# Sheet2.net
KiCad netlist of a schematic drawn in Altium Designer
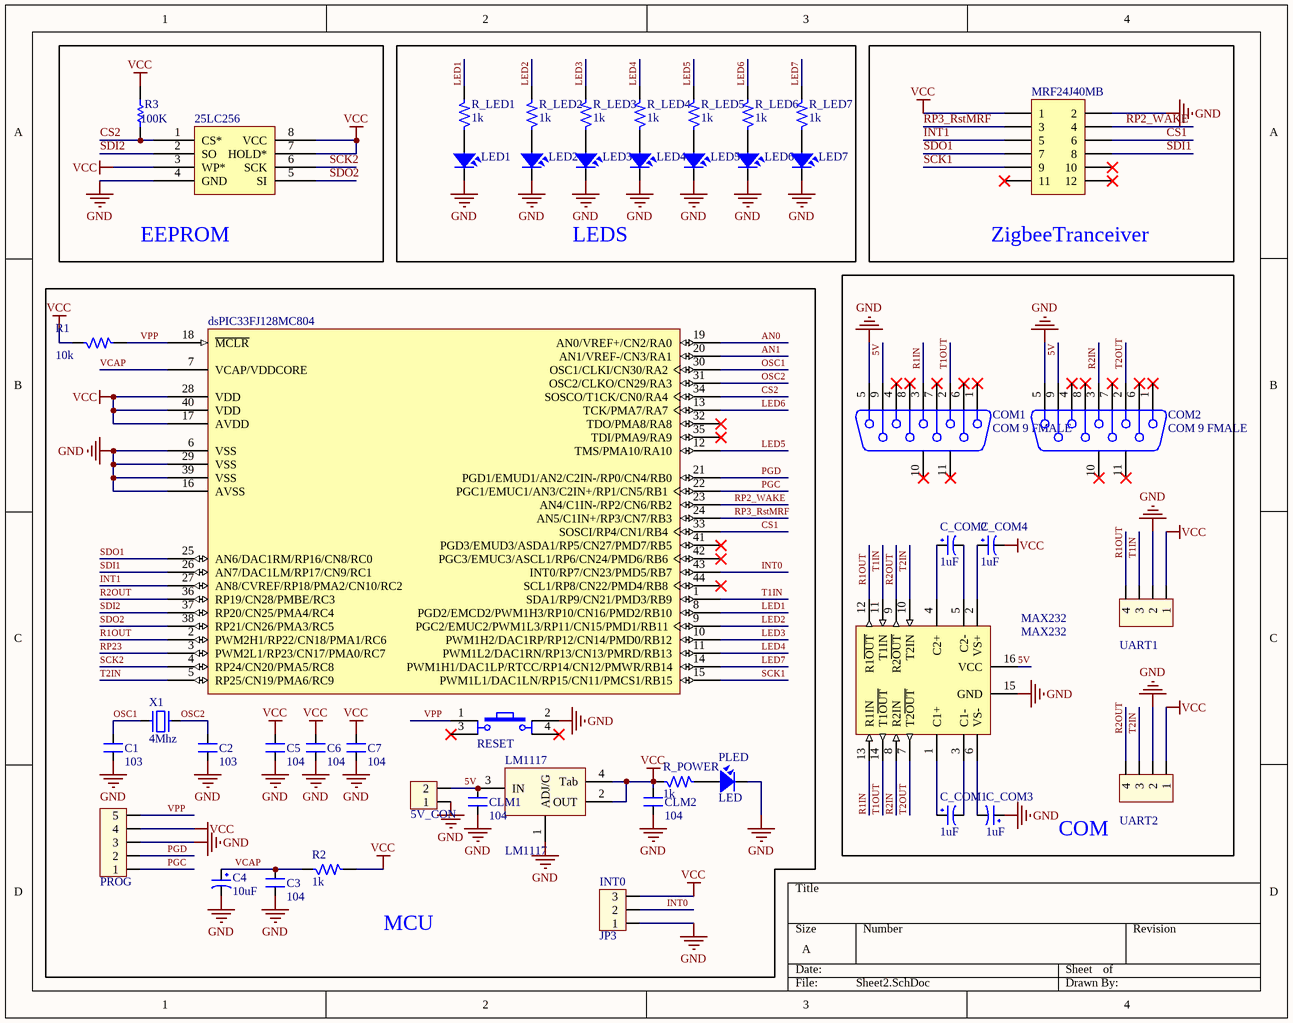
[diagram p0: Sheet2.SchDoc]

(export (version "E")
  (design (tool "Eeschema 10.0.6"))
  (components
    (comp (ref "5V_CON")
      (value "JP2")
      (footprint "CON2")
      (description "Connector 2")
      (libsource (lib "syhaunguyen") (part "Con2"))
    )
    (comp (ref "25LC256") (value "25LC256") (footprint "DIP-8") (libsource (lib "25LC256") (part "25LC256")))
    (comp (ref "C1")
      (value "103")
      (footprint "SM-0805")
      (description "Cap SMD")
      (libsource (lib "syhaunguyen") (part "CM"))
    )
    (comp (ref "C2")
      (value "103")
      (footprint "SM-0805")
      (description "Cap SMD")
      (libsource (lib "syhaunguyen") (part "CM"))
    )
    (comp (ref "C3")
      (value "104")
      (footprint "SM-0805")
      (description "Cap SMD")
      (libsource (lib "syhaunguyen") (part "CM"))
    )
    (comp (ref "C4")
      (value "10uF")
      (footprint "CP1/2")
      (description "Cap P  0,1uF < 22uF , 16 - 50V")
      (libsource (lib "") (part "CP1_1"))
    )
    (comp (ref "C5")
      (value "104")
      (footprint "SM-0805")
      (description "Cap SMD")
      (libsource (lib "syhaunguyen") (part "CM"))
    )
    (comp (ref "C6")
      (value "104")
      (footprint "SM-0805")
      (description "Cap SMD")
      (libsource (lib "syhaunguyen") (part "CM"))
    )
    (comp (ref "C7")
      (value "104")
      (footprint "SM-0805")
      (description "Cap SMD")
      (libsource (lib "syhaunguyen") (part "CM"))
    )
    (comp (ref "CLM1")
      (value "104")
      (footprint "SM-0805")
      (description "Cap np Cremic Value  104pF => 105pF")
      (libsource (lib "syhaunguyen") (part "CN2"))
    )
    (comp (ref "CLM2")
      (value "104")
      (footprint "SM-0805")
      (description "Cap np Cremic Value  104pF => 105pF")
      (libsource (lib "syhaunguyen") (part "CN2"))
    )
    (comp (ref "COM1")
      (value "COM 9 FMALE")
      (footprint "DSB 9-F")
      (description "COM 9")
      (fields (field (name "PUBLISHER") "Altium Limited"))
      (libsource (lib "syhaunguyen") (part "DSB9F"))
    )
    (comp (ref "COM2")
      (value "COM 9 FMALE")
      (footprint "DSB 9-F")
      (description "COM 9")
      (fields (field (name "PUBLISHER") "Altium Limited"))
      (libsource (lib "syhaunguyen") (part "DSB9F"))
    )
    (comp (ref "C_COM1")
      (value "1uF")
      (footprint "CP1/2")
      (description "Cap P  0,1uF < 22uF , 16 - 50V")
      (libsource (lib "syhaunguyen") (part "CP1"))
    )
    (comp (ref "C_COM2")
      (value "1uF")
      (footprint "CP1/2")
      (description "Cap P  0,1uF < 22uF , 16 - 50V")
      (libsource (lib "syhaunguyen") (part "CP1"))
    )
    (comp (ref "C_COM3")
      (value "1uF")
      (footprint "CP1/2")
      (description "Cap P  0,1uF < 22uF , 16 - 50V")
      (libsource (lib "syhaunguyen") (part "CP1"))
    )
    (comp (ref "C_COM4")
      (value "1uF")
      (footprint "CP1/2")
      (description "Cap P  0,1uF < 22uF , 16 - 50V")
      (libsource (lib "syhaunguyen") (part "CP1"))
    )
    (comp (ref "dsPIC33FJ128MC804")
      (value "DSPIC33FJ128MC804T-E/PT")
      (footprint "TQFP44-10x10-P0.8")
      (fields (field (name "PUBLISHER") "Altium Limited"))
      (libsource (lib "Microchip DSC 16-Bit dsPIC33F") (part "DSPIC33FJ128MC804T-E/PT"))
    )
    (comp (ref "INT0")
      (value "JP3")
      (footprint "CON3")
      (description "Connector 3")
      (libsource (lib "syhaunguyen") (part "Con3"))
    )
    (comp (ref "LED1")
      (value "LED")
      (footprint "SM-LED-Red")
      (description "Led  Vuong")
      (libsource (lib "syhaunguyen") (part "LED"))
    )
    (comp (ref "LED2")
      (value "LED")
      (footprint "SM-LED-Red")
      (description "Led  Vuong")
      (libsource (lib "syhaunguyen") (part "LED"))
    )
    (comp (ref "LED3")
      (value "LED")
      (footprint "SM-LED-Red")
      (description "Led  Vuong")
      (libsource (lib "syhaunguyen") (part "LED"))
    )
    (comp (ref "LED4")
      (value "LED")
      (footprint "SM-LED-Red")
      (description "Led  Vuong")
      (libsource (lib "syhaunguyen") (part "LED"))
    )
    (comp (ref "LED5")
      (value "LED")
      (footprint "SM-LED-Red")
      (description "Led  Vuong")
      (libsource (lib "syhaunguyen") (part "LED"))
    )
    (comp (ref "LED6")
      (value "LED")
      (footprint "SM-LED-Red")
      (description "Led  Vuong")
      (libsource (lib "syhaunguyen") (part "LED"))
    )
    (comp (ref "LED7")
      (value "LED")
      (footprint "SM-LED-Red")
      (description "Led  Vuong")
      (libsource (lib "syhaunguyen") (part "LED"))
    )
    (comp (ref "LM1117")
      (value "LM1117")
      (footprint "SOT223-4N")
      (description "3v3")
      (libsource (lib "syhaunguyen") (part "LM1117"))
    )
    (comp (ref "MAX232")
      (value "MAX232")
      (footprint "SOP16")
      (description "Dual EIA-232 Driver/Receiver")
      (libsource (lib "syhaunguyen") (part "MAX232"))
    )
    (comp (ref "MRF24J40MB")
      (value "Header 6X2")
      (footprint "HDR2X6")
      (description "Header, 6-Pin, Dual row")
      (fields (field (name "PUBLISHER") "Altium Limited"))
      (libsource (lib "Miscellaneous Connectors") (part "Header 6X2"))
    )
    (comp (ref "PLED")
      (value "LED")
      (footprint "LED-3")
      (description "Led  Vuong")
      (libsource (lib "syhaunguyen") (part "LED"))
    )
    (comp (ref "PROG")
      (value "JP5")
      (footprint "CON5")
      (description "Connector 5")
      (libsource (lib "syhaunguyen") (part "Con5"))
    )
    (comp (ref "R1")
      (value "10k")
      (footprint "C0805")
      (description "Resistor 1/4W")
      (libsource (lib "syhaunguyen") (part "R"))
    )
    (comp (ref "R2")
      (value "1k")
      (footprint "SM-0805")
      (description "Resistor 1/4W")
      (libsource (lib "syhaunguyen") (part "R"))
    )
    (comp (ref "R3")
      (value "100K")
      (footprint "C0805")
      (description "Semiconductor Resistor")
      (fields (field (name "Comment") "Res Semi") (field (name "PUBLISHER") "Altium Limited"))
      (libsource (lib "Miscellaneous Devices") (part "Res Semi"))
    )
    (comp (ref "RESET")
      (value "SW")
      (footprint "SW2")
      (description "Switch button 4 pin")
      (libsource (lib "syhaunguyen") (part "SW4"))
    )
    (comp (ref "R_LED1")
      (value "1k")
      (footprint "SM-0805")
      (description "Resistor 1/4W")
      (libsource (lib "syhaunguyen") (part "R"))
    )
    (comp (ref "R_LED2")
      (value "1k")
      (footprint "SM-0805")
      (description "Resistor 1/4W")
      (libsource (lib "syhaunguyen") (part "R"))
    )
    (comp (ref "R_LED3")
      (value "1k")
      (footprint "SM-0805")
      (description "Resistor 1/4W")
      (libsource (lib "syhaunguyen") (part "R"))
    )
    (comp (ref "R_LED4")
      (value "1k")
      (footprint "SM-0805")
      (description "Resistor 1/4W")
      (libsource (lib "syhaunguyen") (part "R"))
    )
    (comp (ref "R_LED5")
      (value "1k")
      (footprint "SM-0805")
      (description "Resistor 1/4W")
      (libsource (lib "syhaunguyen") (part "R"))
    )
    (comp (ref "R_LED6")
      (value "1k")
      (footprint "SM-0805")
      (description "Resistor 1/4W")
      (libsource (lib "syhaunguyen") (part "R"))
    )
    (comp (ref "R_LED7")
      (value "1k")
      (footprint "SM-0805")
      (description "Resistor 1/4W")
      (libsource (lib "syhaunguyen") (part "R"))
    )
    (comp (ref "R_POWER")
      (value "1k")
      (footprint "SM-0805")
      (description "Resistor 1/4W")
      (libsource (lib "syhaunguyen") (part "R"))
    )
    (comp (ref "UART1")
      (value "JP4")
      (footprint "CON4")
      (description "Connector 4")
      (libsource (lib "syhaunguyen") (part "Con4"))
    )
    (comp (ref "UART2")
      (value "JP4")
      (footprint "CON4")
      (description "Connector 4")
      (libsource (lib "syhaunguyen") (part "Con4"))
    )
    (comp (ref "X1")
      (value "4Mhz")
      (footprint "THACH ANH 12MHz")
      (description "Crystal For all Crystal 2pin.")
      (libsource (lib "syhaunguyen") (part "XT2"))
    )
  )
  (nets
    (net (code "1") (name "/5V") (class "Default")
      (node (ref "5V_CON") (pin "2") (pinfunction "2_2") (pintype "passive"))
      (node (ref "CLM1") (pin "2") (pinfunction "2_2") (pintype "passive"))
      (node (ref "COM1") (pin "9") (pinfunction "9_9") (pintype "passive"))
      (node (ref "COM2") (pin "9") (pinfunction "9_9") (pintype "passive"))
      (node (ref "LM1117") (pin "3") (pinfunction "IN_3") (pintype "passive"))
      (node (ref "MAX232") (pin "16") (pinfunction "VCC_16") (pintype "power_in"))
    )
    (net (code "2") (name "/AN0") (class "Default")
      (node (ref "dsPIC33FJ128MC804") (pin "19") (pinfunction "AN0/VREF+/CN2/RA0_19") (pintype "bidirectional"))
    )
    (net (code "3") (name "/AN1") (class "Default")
      (node (ref "dsPIC33FJ128MC804") (pin "20") (pinfunction "AN1/VREF-/CN3/RA1_20") (pintype "bidirectional"))
    )
    (net (code "4") (name "/CS1") (class "Default")
      (node (ref "MRF24J40MB") (pin "6") (pinfunction "6_6") (pintype "passive"))
      (node (ref "dsPIC33FJ128MC804") (pin "33") (pinfunction "SOSCI/RP4/CN1/RB4_33") (pintype "bidirectional"))
    )
    (net (code "5") (name "/CS2") (class "Default")
      (node (ref "25LC256") (pin "1") (pinfunction "CS*_1") (pintype "passive"))
      (node (ref "R3") (pin "1") (pinfunction "1_1") (pintype "passive"))
      (node (ref "dsPIC33FJ128MC804") (pin "34") (pinfunction "SOSCO/T1CK/CN0/RA4_34") (pintype "bidirectional"))
    )
    (net (code "6") (name "/INT0") (class "Default")
      (node (ref "INT0") (pin "2") (pinfunction "2_2") (pintype "passive"))
      (node (ref "dsPIC33FJ128MC804") (pin "43") (pinfunction "INT0/RP7/CN23/PMD5/RB7_43") (pintype "bidirectional"))
    )
    (net (code "7") (name "/INT1") (class "Default")
      (node (ref "MRF24J40MB") (pin "5") (pinfunction "5_5") (pintype "passive"))
      (node (ref "dsPIC33FJ128MC804") (pin "27") (pinfunction "AN8/CVREF/RP18/PMA2/CN10/RC2_27") (pintype "bidirectional"))
    )
    (net (code "8") (name "/LED1") (class "Default")
      (node (ref "R_LED1") (pin "2") (pinfunction "2_2") (pintype "passive"))
      (node (ref "dsPIC33FJ128MC804") (pin "8") (pinfunction "PGD2/EMCD2/PWM1H3/RP10/CN16/PMD2/RB10_8") (pintype "bidirectional"))
    )
    (net (code "9") (name "/LED2") (class "Default")
      (node (ref "R_LED2") (pin "2") (pinfunction "2_2") (pintype "passive"))
      (node (ref "dsPIC33FJ128MC804") (pin "9") (pinfunction "PGC2/EMUC2/PWM1L3/RP11/CN15/PMD1/RB11_9") (pintype "bidirectional"))
    )
    (net (code "10") (name "/LED3") (class "Default")
      (node (ref "R_LED3") (pin "2") (pinfunction "2_2") (pintype "passive"))
      (node (ref "dsPIC33FJ128MC804") (pin "10") (pinfunction "PWM1H2/DAC1RP/RP12/CN14/PMD0/RB12_10") (pintype "bidirectional"))
    )
    (net (code "11") (name "/LED4") (class "Default")
      (node (ref "R_LED4") (pin "2") (pinfunction "2_2") (pintype "passive"))
      (node (ref "dsPIC33FJ128MC804") (pin "11") (pinfunction "PWM1L2/DAC1RN/RP13/CN13/PMRD/RB13_11") (pintype "bidirectional"))
    )
    (net (code "12") (name "/LED5") (class "Default")
      (node (ref "R_LED5") (pin "2") (pinfunction "2_2") (pintype "passive"))
      (node (ref "dsPIC33FJ128MC804") (pin "12") (pinfunction "TMS/PMA10/RA10_12") (pintype "bidirectional"))
    )
    (net (code "13") (name "/LED6") (class "Default")
      (node (ref "R_LED6") (pin "2") (pinfunction "2_2") (pintype "passive"))
      (node (ref "dsPIC33FJ128MC804") (pin "13") (pinfunction "TCK/PMA7/RA7_13") (pintype "bidirectional"))
    )
    (net (code "14") (name "/LED7") (class "Default")
      (node (ref "R_LED7") (pin "2") (pinfunction "2_2") (pintype "passive"))
      (node (ref "dsPIC33FJ128MC804") (pin "14") (pinfunction "PWM1H1/DAC1LP/RTCC/RP14/CN12/PMWR/RB14_14") (pintype "bidirectional"))
    )
    (net (code "15") (name "/OSC1") (class "Default")
      (node (ref "C1") (pin "2") (pinfunction "2_2") (pintype "passive"))
      (node (ref "X1") (pin "1") (pinfunction "1_1") (pintype "passive"))
      (node (ref "dsPIC33FJ128MC804") (pin "30") (pinfunction "OSC1/CLKI/CN30/RA2_30") (pintype "bidirectional"))
    )
    (net (code "16") (name "/OSC2") (class "Default")
      (node (ref "C2") (pin "2") (pinfunction "2_2") (pintype "passive"))
      (node (ref "X1") (pin "2") (pinfunction "2_2") (pintype "passive"))
      (node (ref "dsPIC33FJ128MC804") (pin "31") (pinfunction "OSC2/CLKO/CN29/RA3_31") (pintype "bidirectional"))
    )
    (net (code "17") (name "/PGC") (class "Default")
      (node (ref "PROG") (pin "1") (pinfunction "1_1") (pintype "passive"))
      (node (ref "dsPIC33FJ128MC804") (pin "22") (pinfunction "PGC1/EMUC1/AN3/C2IN+/RP1/CN5/RB1_22") (pintype "bidirectional"))
    )
    (net (code "18") (name "/PGD") (class "Default")
      (node (ref "PROG") (pin "2") (pinfunction "2_2") (pintype "passive"))
      (node (ref "dsPIC33FJ128MC804") (pin "21") (pinfunction "PGD1/EMUD1/AN2/C2IN-/RP0/CN4/RB0_21") (pintype "bidirectional"))
    )
    (net (code "19") (name "/R1IN") (class "Default")
      (node (ref "COM1") (pin "3") (pinfunction "3_3") (pintype "passive"))
      (node (ref "MAX232") (pin "13") (pinfunction "R1IN_13") (pintype "input"))
    )
    (net (code "20") (name "/R1OUT") (class "Default")
      (node (ref "MAX232") (pin "12") (pinfunction "R1~{OUT}_12") (pintype "output"))
      (node (ref "UART1") (pin "4") (pinfunction "4_4") (pintype "passive"))
      (node (ref "dsPIC33FJ128MC804") (pin "2") (pinfunction "PWM2H1/RP22/CN18/PMA1/RC6_2") (pintype "bidirectional"))
    )
    (net (code "21") (name "/R2IN") (class "Default")
      (node (ref "COM2") (pin "3") (pinfunction "3_3") (pintype "passive"))
      (node (ref "MAX232") (pin "8") (pinfunction "R2IN_8") (pintype "input"))
    )
    (net (code "22") (name "/R2OUT") (class "Default")
      (node (ref "MAX232") (pin "9") (pinfunction "R2~{OUT}_9") (pintype "output"))
      (node (ref "UART2") (pin "4") (pinfunction "4_4") (pintype "passive"))
      (node (ref "dsPIC33FJ128MC804") (pin "36") (pinfunction "RP19/CN28/PMBE/RC3_36") (pintype "bidirectional"))
    )
    (net (code "23") (name "/RP2_WAKE") (class "Default")
      (node (ref "MRF24J40MB") (pin "4") (pinfunction "4_4") (pintype "passive"))
      (node (ref "dsPIC33FJ128MC804") (pin "23") (pinfunction "AN4/C1IN-/RP2/CN6/RB2_23") (pintype "bidirectional"))
    )
    (net (code "24") (name "/RP3_RstMRF") (class "Default")
      (node (ref "MRF24J40MB") (pin "3") (pinfunction "3_3") (pintype "passive"))
      (node (ref "dsPIC33FJ128MC804") (pin "24") (pinfunction "AN5/C1IN+/RP3/CN7/RB3_24") (pintype "bidirectional"))
    )
    (net (code "25") (name "/RP23") (class "Default")
      (node (ref "dsPIC33FJ128MC804") (pin "3") (pinfunction "PWM2L1/RP23/CN17/PMA0/RC7_3") (pintype "bidirectional"))
    )
    (net (code "26") (name "/SCK1") (class "Default")
      (node (ref "MRF24J40MB") (pin "9") (pinfunction "9_9") (pintype "passive"))
      (node (ref "dsPIC33FJ128MC804") (pin "15") (pinfunction "PWM1L1/DAC1LN/RP15/CN11/PMCS1/RB15_15") (pintype "bidirectional"))
    )
    (net (code "27") (name "/SCK2") (class "Default")
      (node (ref "25LC256") (pin "6") (pinfunction "SCK_6") (pintype "passive"))
      (node (ref "dsPIC33FJ128MC804") (pin "4") (pinfunction "RP24/CN20/PMA5/RC8_4") (pintype "bidirectional"))
    )
    (net (code "28") (name "/SDI1") (class "Default")
      (node (ref "MRF24J40MB") (pin "8") (pinfunction "8_8") (pintype "passive"))
      (node (ref "dsPIC33FJ128MC804") (pin "26") (pinfunction "AN7/DAC1LM/RP17/CN9/RC1_26") (pintype "bidirectional"))
    )
    (net (code "29") (name "/SDI2") (class "Default")
      (node (ref "25LC256") (pin "2") (pinfunction "SO_2") (pintype "passive"))
      (node (ref "dsPIC33FJ128MC804") (pin "37") (pinfunction "RP20/CN25/PMA4/RC4_37") (pintype "bidirectional"))
    )
    (net (code "30") (name "/SDO1") (class "Default")
      (node (ref "MRF24J40MB") (pin "7") (pinfunction "7_7") (pintype "passive"))
      (node (ref "dsPIC33FJ128MC804") (pin "25") (pinfunction "AN6/DAC1RM/RP16/CN8/RC0_25") (pintype "bidirectional"))
    )
    (net (code "31") (name "/SDO2") (class "Default")
      (node (ref "25LC256") (pin "5") (pinfunction "SI_5") (pintype "passive"))
      (node (ref "dsPIC33FJ128MC804") (pin "38") (pinfunction "RP21/CN26/PMA3/RC5_38") (pintype "bidirectional"))
    )
    (net (code "32") (name "/T1IN") (class "Default")
      (node (ref "MAX232") (pin "11") (pinfunction "T1IN_11") (pintype "input"))
      (node (ref "UART1") (pin "3") (pinfunction "3_3") (pintype "passive"))
      (node (ref "dsPIC33FJ128MC804") (pin "1") (pinfunction "SDA1/RP9/CN21/PMD3/RB9_1") (pintype "bidirectional"))
    )
    (net (code "33") (name "/T1OUT") (class "Default")
      (node (ref "COM1") (pin "2") (pinfunction "2_2") (pintype "passive"))
      (node (ref "MAX232") (pin "14") (pinfunction "T1~{OUT}_14") (pintype "output"))
    )
    (net (code "34") (name "/T2IN") (class "Default")
      (node (ref "MAX232") (pin "10") (pinfunction "T2IN_10") (pintype "input"))
      (node (ref "UART2") (pin "3") (pinfunction "3_3") (pintype "passive"))
      (node (ref "dsPIC33FJ128MC804") (pin "5") (pinfunction "RP25/CN19/PMA6/RC9_5") (pintype "bidirectional"))
    )
    (net (code "35") (name "/T2OUT") (class "Default")
      (node (ref "COM2") (pin "2") (pinfunction "2_2") (pintype "passive"))
      (node (ref "MAX232") (pin "7") (pinfunction "T2~{OUT}_7") (pintype "output"))
    )
    (net (code "36") (name "/VCAP") (class "Default")
      (node (ref "C3") (pin "2") (pinfunction "2_2") (pintype "passive"))
      (node (ref "C4") (pin "1") (pinfunction "1_1") (pintype "passive"))
      (node (ref "R2") (pin "1") (pinfunction "1_1") (pintype "passive"))
      (node (ref "dsPIC33FJ128MC804") (pin "7") (pinfunction "VCAP/VDDCORE_7") (pintype "power_in"))
    )
    (net (code "37") (name "/VPP") (class "Default")
      (node (ref "PROG") (pin "5") (pinfunction "5_5") (pintype "passive"))
      (node (ref "R1") (pin "2") (pinfunction "2_2") (pintype "passive"))
      (node (ref "RESET") (pin "1") (pintype "passive"))
      (node (ref "dsPIC33FJ128MC804") (pin "18") (pinfunction "~{MCLR}_18") (pintype "input"))
    )
    (net (code "38") (name "GND") (class "Default")
      (node (ref "25LC256") (pin "4") (pinfunction "GND_4") (pintype "power_in"))
      (node (ref "5V_CON") (pin "1") (pinfunction "1_1") (pintype "passive"))
      (node (ref "C1") (pin "1") (pinfunction "1_1") (pintype "passive"))
      (node (ref "C2") (pin "1") (pinfunction "1_1") (pintype "passive"))
      (node (ref "C3") (pin "1") (pinfunction "1_1") (pintype "passive"))
      (node (ref "C4") (pin "2") (pinfunction "2_2") (pintype "passive"))
      (node (ref "C5") (pin "1") (pinfunction "1_1") (pintype "passive"))
      (node (ref "C6") (pin "1") (pinfunction "1_1") (pintype "passive"))
      (node (ref "C7") (pin "1") (pinfunction "1_1") (pintype "passive"))
      (node (ref "CLM1") (pin "1") (pinfunction "1_1") (pintype "passive"))
      (node (ref "CLM2") (pin "1") (pinfunction "1_1") (pintype "passive"))
      (node (ref "COM1") (pin "5") (pinfunction "5_5") (pintype "passive"))
      (node (ref "COM2") (pin "5") (pinfunction "5_5") (pintype "passive"))
      (node (ref "C_COM3") (pin "1") (pinfunction "1_1") (pintype "passive"))
      (node (ref "INT0") (pin "1") (pinfunction "1_1") (pintype "passive"))
      (node (ref "LED1") (pin "2") (pinfunction "2_2") (pintype "passive"))
      (node (ref "LED2") (pin "2") (pinfunction "2_2") (pintype "passive"))
      (node (ref "LED3") (pin "2") (pinfunction "2_2") (pintype "passive"))
      (node (ref "LED4") (pin "2") (pinfunction "2_2") (pintype "passive"))
      (node (ref "LED5") (pin "2") (pinfunction "2_2") (pintype "passive"))
      (node (ref "LED6") (pin "2") (pinfunction "2_2") (pintype "passive"))
      (node (ref "LED7") (pin "2") (pinfunction "2_2") (pintype "passive"))
      (node (ref "LM1117") (pin "1") (pinfunction "ADJ/G_1") (pintype "passive"))
      (node (ref "MAX232") (pin "15") (pinfunction "GND_15") (pintype "power_in"))
      (node (ref "MRF24J40MB") (pin "2") (pinfunction "2_2") (pintype "passive"))
      (node (ref "PLED") (pin "2") (pinfunction "2_2") (pintype "passive"))
      (node (ref "PROG") (pin "3") (pinfunction "3_3") (pintype "passive"))
      (node (ref "RESET") (pin "2") (pintype "passive"))
      (node (ref "UART1") (pin "2") (pinfunction "2_2") (pintype "passive"))
      (node (ref "UART2") (pin "2") (pinfunction "2_2") (pintype "passive"))
      (node (ref "dsPIC33FJ128MC804") (pin "16") (pinfunction "AVSS_16") (pintype "power_in"))
      (node (ref "dsPIC33FJ128MC804") (pin "29") (pinfunction "VSS_29") (pintype "power_in"))
      (node (ref "dsPIC33FJ128MC804") (pin "39") (pinfunction "VSS_39") (pintype "power_in"))
      (node (ref "dsPIC33FJ128MC804") (pin "6") (pinfunction "VSS_6") (pintype "power_in"))
    )
    (net (code "39") (name "Net-(LED1-Pad1)") (class "Default")
      (node (ref "LED1") (pin "1") (pinfunction "1_1") (pintype "passive"))
      (node (ref "R_LED1") (pin "1") (pinfunction "1_1") (pintype "passive"))
    )
    (net (code "40") (name "Net-(LED2-Pad1)") (class "Default")
      (node (ref "LED2") (pin "1") (pinfunction "1_1") (pintype "passive"))
      (node (ref "R_LED2") (pin "1") (pinfunction "1_1") (pintype "passive"))
    )
    (net (code "41") (name "Net-(LED3-Pad1)") (class "Default")
      (node (ref "LED3") (pin "1") (pinfunction "1_1") (pintype "passive"))
      (node (ref "R_LED3") (pin "1") (pinfunction "1_1") (pintype "passive"))
    )
    (net (code "42") (name "Net-(LED4-Pad1)") (class "Default")
      (node (ref "LED4") (pin "1") (pinfunction "1_1") (pintype "passive"))
      (node (ref "R_LED4") (pin "1") (pinfunction "1_1") (pintype "passive"))
    )
    (net (code "43") (name "Net-(LED5-Pad1)") (class "Default")
      (node (ref "LED5") (pin "1") (pinfunction "1_1") (pintype "passive"))
      (node (ref "R_LED5") (pin "1") (pinfunction "1_1") (pintype "passive"))
    )
    (net (code "44") (name "Net-(LED6-Pad1)") (class "Default")
      (node (ref "LED6") (pin "1") (pinfunction "1_1") (pintype "passive"))
      (node (ref "R_LED6") (pin "1") (pinfunction "1_1") (pintype "passive"))
    )
    (net (code "45") (name "Net-(LED7-Pad1)") (class "Default")
      (node (ref "LED7") (pin "1") (pinfunction "1_1") (pintype "passive"))
      (node (ref "R_LED7") (pin "1") (pinfunction "1_1") (pintype "passive"))
    )
    (net (code "46") (name "Net-(MAX232-C1+)") (class "Default")
      (node (ref "C_COM1") (pin "1") (pinfunction "1_1") (pintype "passive"))
      (node (ref "MAX232") (pin "1") (pinfunction "C1+_1") (pintype "passive"))
    )
    (net (code "47") (name "Net-(MAX232-C1-)") (class "Default")
      (node (ref "C_COM1") (pin "2") (pinfunction "2_2") (pintype "passive"))
      (node (ref "MAX232") (pin "3") (pinfunction "C1-_3") (pintype "passive"))
    )
    (net (code "48") (name "Net-(MAX232-C2+)") (class "Default")
      (node (ref "C_COM2") (pin "1") (pinfunction "1_1") (pintype "passive"))
      (node (ref "MAX232") (pin "4") (pinfunction "C2+_4") (pintype "passive"))
    )
    (net (code "49") (name "Net-(MAX232-C2-)") (class "Default")
      (node (ref "C_COM2") (pin "2") (pinfunction "2_2") (pintype "passive"))
      (node (ref "MAX232") (pin "5") (pinfunction "C2-_5") (pintype "passive"))
    )
    (net (code "50") (name "Net-(MAX232-VS+)") (class "Default")
      (node (ref "C_COM4") (pin "1") (pinfunction "1_1") (pintype "passive"))
      (node (ref "MAX232") (pin "2") (pinfunction "VS+_2") (pintype "power_in"))
    )
    (net (code "51") (name "Net-(MAX232-VS-)") (class "Default")
      (node (ref "C_COM3") (pin "2") (pinfunction "2_2") (pintype "passive"))
      (node (ref "MAX232") (pin "6") (pinfunction "VS-_6") (pintype "power_in"))
    )
    (net (code "52") (name "Net-(PLED-Pad1)") (class "Default")
      (node (ref "PLED") (pin "1") (pinfunction "1_1") (pintype "passive"))
      (node (ref "R_POWER") (pin "2") (pinfunction "2_2") (pintype "passive"))
    )
    (net (code "53") (name "VCC") (class "Default")
      (node (ref "25LC256") (pin "3") (pinfunction "WP*_3") (pintype "passive"))
      (node (ref "25LC256") (pin "7") (pinfunction "HOLD*_7") (pintype "passive"))
      (node (ref "25LC256") (pin "8") (pinfunction "VCC_8") (pintype "power_in"))
      (node (ref "C5") (pin "2") (pinfunction "2_2") (pintype "passive"))
      (node (ref "C6") (pin "2") (pinfunction "2_2") (pintype "passive"))
      (node (ref "C7") (pin "2") (pinfunction "2_2") (pintype "passive"))
      (node (ref "CLM2") (pin "2") (pinfunction "2_2") (pintype "passive"))
      (node (ref "C_COM4") (pin "2") (pinfunction "2_2") (pintype "passive"))
      (node (ref "INT0") (pin "3") (pinfunction "3_3") (pintype "passive"))
      (node (ref "LM1117") (pin "2") (pinfunction "OUT_2") (pintype "passive"))
      (node (ref "LM1117") (pin "4") (pinfunction "Tab_4") (pintype "passive"))
      (node (ref "MRF24J40MB") (pin "1") (pinfunction "1_1") (pintype "passive"))
      (node (ref "PROG") (pin "4") (pinfunction "4_4") (pintype "passive"))
      (node (ref "R1") (pin "1") (pinfunction "1_1") (pintype "passive"))
      (node (ref "R2") (pin "2") (pinfunction "2_2") (pintype "passive"))
      (node (ref "R3") (pin "2") (pinfunction "2_2") (pintype "passive"))
      (node (ref "R_POWER") (pin "1") (pinfunction "1_1") (pintype "passive"))
      (node (ref "UART1") (pin "1") (pinfunction "1_1") (pintype "passive"))
      (node (ref "UART2") (pin "1") (pinfunction "1_1") (pintype "passive"))
      (node (ref "dsPIC33FJ128MC804") (pin "17") (pinfunction "AVDD_17") (pintype "power_in"))
      (node (ref "dsPIC33FJ128MC804") (pin "28") (pinfunction "VDD_28") (pintype "power_in"))
      (node (ref "dsPIC33FJ128MC804") (pin "40") (pinfunction "VDD_40") (pintype "power_in"))
    )
    (net (code "54") (name "unconnected-(COM1-MH1-Pad10)") (class "Default")
      (node (ref "COM1") (pin "10") (pinfunction "MH1_10") (pintype "passive+no_connect"))
    )
    (net (code "55") (name "unconnected-(COM1-MH2-Pad11)") (class "Default")
      (node (ref "COM1") (pin "11") (pinfunction "MH2_11") (pintype "passive+no_connect"))
    )
    (net (code "56") (name "unconnected-(COM1-Pad1)") (class "Default")
      (node (ref "COM1") (pin "1") (pinfunction "1_1") (pintype "passive+no_connect"))
    )
    (net (code "57") (name "unconnected-(COM1-Pad4)") (class "Default")
      (node (ref "COM1") (pin "4") (pinfunction "4_4") (pintype "passive+no_connect"))
    )
    (net (code "58") (name "unconnected-(COM1-Pad6)") (class "Default")
      (node (ref "COM1") (pin "6") (pinfunction "6_6") (pintype "passive+no_connect"))
    )
    (net (code "59") (name "unconnected-(COM1-Pad7)") (class "Default")
      (node (ref "COM1") (pin "7") (pinfunction "7_7") (pintype "passive+no_connect"))
    )
    (net (code "60") (name "unconnected-(COM1-Pad8)") (class "Default")
      (node (ref "COM1") (pin "8") (pinfunction "8_8") (pintype "passive+no_connect"))
    )
    (net (code "61") (name "unconnected-(COM2-MH1-Pad10)") (class "Default")
      (node (ref "COM2") (pin "10") (pinfunction "MH1_10") (pintype "passive+no_connect"))
    )
    (net (code "62") (name "unconnected-(COM2-MH2-Pad11)") (class "Default")
      (node (ref "COM2") (pin "11") (pinfunction "MH2_11") (pintype "passive+no_connect"))
    )
    (net (code "63") (name "unconnected-(COM2-Pad1)") (class "Default")
      (node (ref "COM2") (pin "1") (pinfunction "1_1") (pintype "passive+no_connect"))
    )
    (net (code "64") (name "unconnected-(COM2-Pad4)") (class "Default")
      (node (ref "COM2") (pin "4") (pinfunction "4_4") (pintype "passive+no_connect"))
    )
    (net (code "65") (name "unconnected-(COM2-Pad6)") (class "Default")
      (node (ref "COM2") (pin "6") (pinfunction "6_6") (pintype "passive+no_connect"))
    )
    (net (code "66") (name "unconnected-(COM2-Pad7)") (class "Default")
      (node (ref "COM2") (pin "7") (pinfunction "7_7") (pintype "passive+no_connect"))
    )
    (net (code "67") (name "unconnected-(COM2-Pad8)") (class "Default")
      (node (ref "COM2") (pin "8") (pinfunction "8_8") (pintype "passive+no_connect"))
    )
    (net (code "68") (name "unconnected-(MRF24J40MB-Pad10)") (class "Default")
      (node (ref "MRF24J40MB") (pin "10") (pinfunction "10_10") (pintype "passive+no_connect"))
    )
    (net (code "69") (name "unconnected-(MRF24J40MB-Pad11)") (class "Default")
      (node (ref "MRF24J40MB") (pin "11") (pinfunction "11_11") (pintype "passive+no_connect"))
    )
    (net (code "70") (name "unconnected-(MRF24J40MB-Pad12)") (class "Default")
      (node (ref "MRF24J40MB") (pin "12") (pinfunction "12_12") (pintype "passive+no_connect"))
    )
    (net (code "71") (name "unconnected-(RESET-Pad3)") (class "Default")
      (node (ref "RESET") (pin "3") (pintype "passive+no_connect"))
    )
    (net (code "72") (name "unconnected-(RESET-Pad4)") (class "Default")
      (node (ref "RESET") (pin "4") (pintype "passive+no_connect"))
    )
    (net (code "73") (name "unconnected-(dsPIC33FJ128MC804-PGC3{slash}EMUC3{slash}ASCL1{slash}RP6{slash}CN24{slash}PMD6{slash}RB6-Pad42)") (class "Default")
      (node (ref "dsPIC33FJ128MC804") (pin "42") (pinfunction "PGC3/EMUC3/ASCL1/RP6/CN24/PMD6/RB6_42") (pintype "bidirectional+no_connect"))
    )
    (net (code "74") (name "unconnected-(dsPIC33FJ128MC804-PGD3{slash}EMUD3{slash}ASDA1{slash}RP5{slash}CN27{slash}PMD7{slash}RB5-Pad41)") (class "Default")
      (node (ref "dsPIC33FJ128MC804") (pin "41") (pinfunction "PGD3/EMUD3/ASDA1/RP5/CN27/PMD7/RB5_41") (pintype "bidirectional+no_connect"))
    )
    (net (code "75") (name "unconnected-(dsPIC33FJ128MC804-SCL1{slash}RP8{slash}CN22{slash}PMD4{slash}RB8-Pad44)") (class "Default")
      (node (ref "dsPIC33FJ128MC804") (pin "44") (pinfunction "SCL1/RP8/CN22/PMD4/RB8_44") (pintype "bidirectional+no_connect"))
    )
    (net (code "76") (name "unconnected-(dsPIC33FJ128MC804-TDI{slash}PMA9{slash}RA9-Pad35)") (class "Default")
      (node (ref "dsPIC33FJ128MC804") (pin "35") (pinfunction "TDI/PMA9/RA9_35") (pintype "bidirectional+no_connect"))
    )
    (net (code "77") (name "unconnected-(dsPIC33FJ128MC804-TDO{slash}PMA8{slash}RA8-Pad32)") (class "Default")
      (node (ref "dsPIC33FJ128MC804") (pin "32") (pinfunction "TDO/PMA8/RA8_32") (pintype "bidirectional+no_connect"))
    )
  )
)
